# Sequencer.net
KiCad netlist of a schematic drawn in Altium Designer
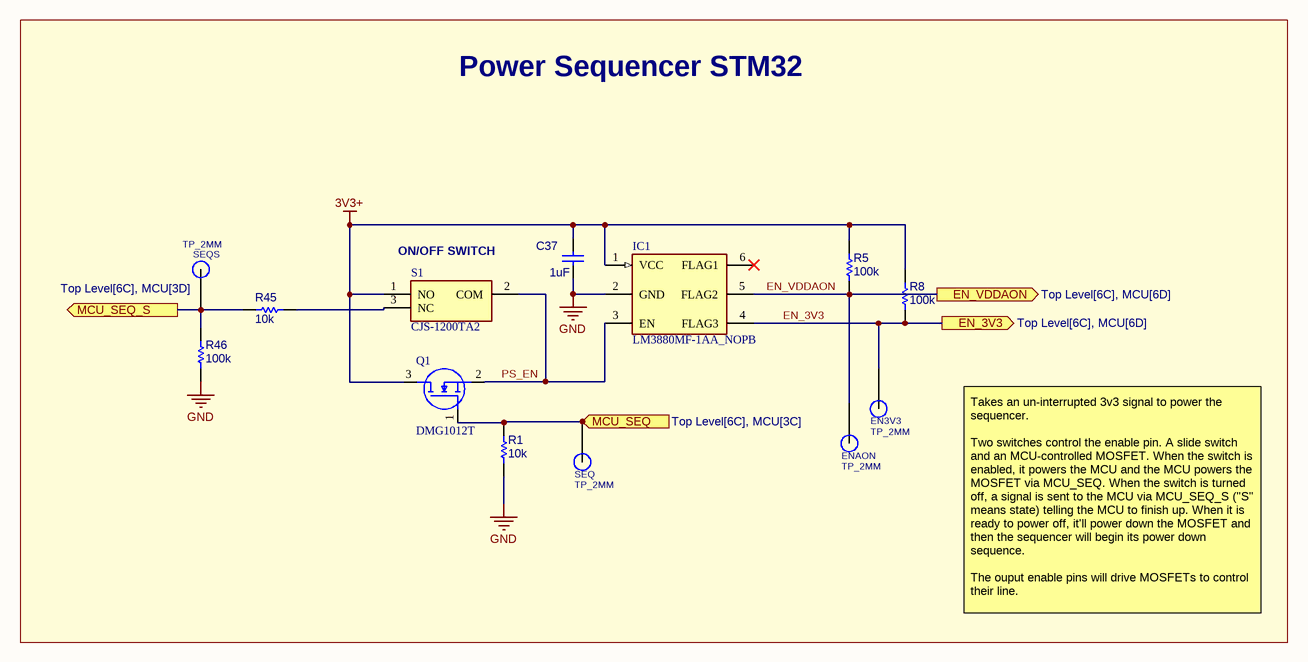
[diagram p0: Sequencer.SchDoc]

(export (version "E")
  (design (tool "Eeschema 10.0.6"))
  (components
    (comp (ref "C37")
      (value "1uF")
      (footprint "C0603")
      (description "Capacitor, MLCC, 100nF, 6V3, X5R, 10%, 0603, T=0,8mm")
      (fields
        (field (name "MANUFACTURER PART NUMBER") "CC0603KRX5R5BB104")
        (field (name "MANUFACTURER") "YAGEO")
        (field (name "PROVIDED_BY") "SUBCO")
      )
      (libsource (lib "Perth Aerospace Student Team") (part "CMP-035-000015-1"))
    )
    (comp (ref "EN3V3") (value "TP_2MM") (footprint "TESTPOINT 2MM") (libsource (lib "C2S") (part "TP_2MM")))
    (comp (ref "ENAON") (value "TP_2MM") (footprint "TESTPOINT 2MM") (libsource (lib "C2S") (part "TP_2MM")))
    (comp (ref "IC1")
      (value "LM3880MF-1AA_NOPB")
      (footprint "LM3880MF-1AA_NOPB")
      (description "Integrated Circuit")
      (fields
        (field (name "MANUFACTURER_PART_NUMBER") "LM3880MF-1AA/NOPB")
        (field (name "MOUSER PART NUMBER") "926-LM3880MF-1AANOPB")
      )
      (libsource (lib "C2Sv0 - Processor") (part "LM3880MF-1AA_NOPB"))
    )
    (comp (ref "Q1")
      (value "DMG1012T")
      (footprint "SOT50P160X90-3N")
      (description "MOSFET (N-Channel)")
      (libsource (lib "C2S") (part "DMG1012T"))
    )
    (comp (ref "R1")
      (value "10k")
      (footprint "RESC1608X55X25ML10T15-1")
      (description "Chip Resistor, 10k Ohm, 0.1 W, -55 to 155 degC, 0603 (1608 Metric)")
      (fields
        (field (name "POWER") "100mW")
        (field (name "TOLERANCE") "1%")
        (field (name "CREATED BY") "Micah Randall")
      )
      (libsource (lib "Perth Aerospace Student Team") (part "CMP-009-00006-5"))
    )
    (comp (ref "R5")
      (value "100k")
      (footprint "RESC1608X55X25ML10T15-1")
      (description "Chip Resistor, 10k Ohm, 0.1 W, -55 to 155 degC, 0603 (1608 Metric)")
      (fields
        (field (name "POWER") "100mW")
        (field (name "TOLERANCE") "1%")
        (field (name "CREATED BY") "Micah Randall")
      )
      (libsource (lib "Perth Aerospace Student Team") (part "CMP-009-00006-5"))
    )
    (comp (ref "R8")
      (value "100k")
      (footprint "RESC1608X55X25ML10T15-1")
      (description "Chip Resistor, 10k Ohm, 0.1 W, -55 to 155 degC, 0603 (1608 Metric)")
      (fields
        (field (name "POWER") "100mW")
        (field (name "TOLERANCE") "1%")
        (field (name "CREATED BY") "Micah Randall")
      )
      (libsource (lib "Perth Aerospace Student Team") (part "CMP-009-00006-5"))
    )
    (comp (ref "R45")
      (value "10k")
      (footprint "RESC1608X55X25ML10T15-1")
      (description "Chip Resistor, 10k Ohm, 0.1 W, -55 to 155 degC, 0603 (1608 Metric)")
      (fields
        (field (name "POWER") "100mW")
        (field (name "TOLERANCE") "1%")
        (field (name "CREATED BY") "Micah Randall")
      )
      (libsource (lib "Perth Aerospace Student Team") (part "CMP-009-00006-5"))
    )
    (comp (ref "R46")
      (value "100k")
      (footprint "RESC1608X55X25ML10T15-1")
      (description "Chip Resistor, 10k Ohm, 0.1 W, -55 to 155 degC, 0603 (1608 Metric)")
      (fields
        (field (name "POWER") "100mW")
        (field (name "TOLERANCE") "1%")
        (field (name "CREATED BY") "Micah Randall")
      )
      (libsource (lib "Perth Aerospace Student Team") (part "CMP-009-00006-5"))
    )
    (comp (ref "S1")
      (value "CJS-1200TA2")
      (footprint "CJS1200TA2")
      (description "Switch")
      (fields (field (name "MOUSER PART NUMBER") "229-CJS-1200TA2"))
      (libsource (lib "C2S") (part "CJS-1200TA2"))
    )
    (comp (ref "SEQ") (value "TP_2MM") (footprint "TESTPOINT 2MM") (libsource (lib "C2S") (part "TP_2MM")))
    (comp (ref "SEQS") (value "TP_2MM") (footprint "TESTPOINT 2MM") (libsource (lib "C2S") (part "TP_2MM")))
  )
  (nets
    (net (code "1") (name "/EN_3V3") (class "Default")
      (node (ref "EN3V3") (pin "TP") (pinfunction "TP_2MM_TP") (pintype "passive"))
      (node (ref "IC1") (pin "4") (pinfunction "FLAG3_4") (pintype "passive"))
      (node (ref "R8") (pin "2") (pinfunction "2_2") (pintype "passive"))
    )
    (net (code "2") (name "/EN_VDDAON") (class "Default")
      (node (ref "ENAON") (pin "TP") (pinfunction "TP_2MM_TP") (pintype "passive"))
      (node (ref "IC1") (pin "5") (pinfunction "FLAG2_5") (pintype "passive"))
      (node (ref "R5") (pin "2") (pinfunction "2_2") (pintype "passive"))
    )
    (net (code "3") (name "/MCU_SEQ") (class "Default")
      (node (ref "Q1") (pin "1") (pinfunction "G_1") (pintype "passive"))
      (node (ref "R1") (pin "1") (pinfunction "1_1") (pintype "passive"))
      (node (ref "SEQ") (pin "TP") (pinfunction "TP_2MM_TP") (pintype "passive"))
    )
    (net (code "4") (name "/MCU_SEQ_S") (class "Default")
      (node (ref "R45") (pin "1") (pinfunction "1_1") (pintype "passive"))
      (node (ref "R46") (pin "1") (pinfunction "1_1") (pintype "passive"))
      (node (ref "SEQS") (pin "TP") (pinfunction "TP_2MM_TP") (pintype "passive"))
    )
    (net (code "5") (name "/PS_EN") (class "Default")
      (node (ref "IC1") (pin "3") (pinfunction "EN_3") (pintype "passive"))
      (node (ref "Q1") (pin "2") (pinfunction "S_2") (pintype "passive"))
      (node (ref "S1") (pin "2") (pinfunction "COM_2") (pintype "passive"))
    )
    (net (code "6") (name "3V3+") (class "Default")
      (node (ref "C37") (pin "2") (pinfunction "2_2") (pintype "passive"))
      (node (ref "IC1") (pin "1") (pinfunction "VCC_1") (pintype "input"))
      (node (ref "Q1") (pin "3") (pinfunction "D_3") (pintype "passive"))
      (node (ref "R5") (pin "1") (pinfunction "1_1") (pintype "passive"))
      (node (ref "R8") (pin "1") (pinfunction "1_1") (pintype "passive"))
      (node (ref "S1") (pin "1") (pinfunction "NO_1") (pintype "passive"))
    )
    (net (code "7") (name "GND") (class "Default")
      (node (ref "C37") (pin "1") (pinfunction "1_1") (pintype "passive"))
      (node (ref "IC1") (pin "2") (pinfunction "GND_2") (pintype "passive"))
      (node (ref "R1") (pin "2") (pinfunction "2_2") (pintype "passive"))
      (node (ref "R46") (pin "2") (pinfunction "2_2") (pintype "passive"))
    )
    (net (code "8") (name "Net-(S1-NC)") (class "Default")
      (node (ref "R45") (pin "2") (pinfunction "2_2") (pintype "passive"))
      (node (ref "S1") (pin "3") (pinfunction "NC_3") (pintype "passive"))
    )
    (net (code "9") (name "unconnected-(IC1-FLAG1-Pad6)") (class "Default")
      (node (ref "IC1") (pin "6") (pinfunction "FLAG1_6") (pintype "passive+no_connect"))
    )
  )
)
